# RF-CONNECTOR.net
KiCad netlist of a schematic drawn in Altium Designer
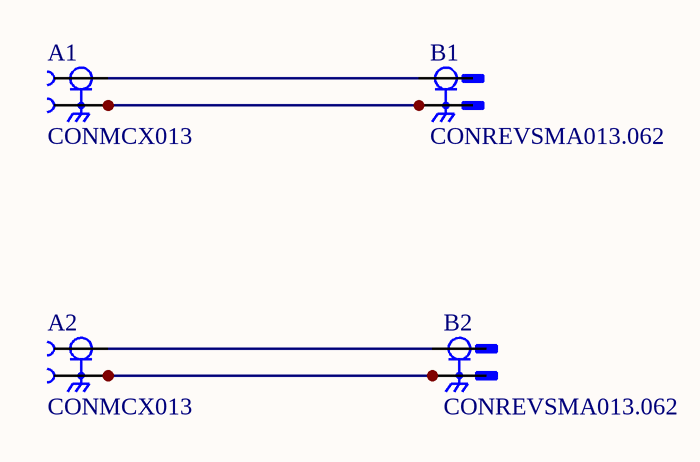
[diagram p0: RF-CONNECTOR.SchDoc]

(export (version "E")
  (design (tool "Eeschema 10.0.6"))
  (components
    (comp (ref "A1")
      (value "CONMCX013")
      (footprint "LINX_CONMCX013")
      (fields (field (name "MF") "Linx Technologies"))
      (libsource (lib "lib") (part "CONMCX013"))
    )
    (comp (ref "A2")
      (value "CONMCX013")
      (footprint "LINX_CONMCX013")
      (fields (field (name "MF") "Linx Technologies"))
      (libsource (lib "lib") (part "CONMCX013"))
    )
    (comp (ref "B1")
      (value "CONREVSMA013.062")
      (footprint "LINX_CONREVSMA013.031")
      (description "CONN RPSMA PLG STR 50OHM EDGEMNT")
      (fields (field (name "MF") "Linx"))
      (libsource (lib "lib") (part "CONREVSMA013.031"))
    )
    (comp (ref "B2")
      (value "CONREVSMA013.062")
      (footprint "LINX_CONREVSMA013.031")
      (description "CONN RPSMA PLG STR 50OHM EDGEMNT")
      (fields (field (name "MF") "Linx"))
      (libsource (lib "lib") (part "CONREVSMA013.031"))
    )
  )
  (nets
    (net (code "1") (name "Net-(A1-2-PadG1)") (class "Default")
      (node (ref "A1") (pin "G1") (pinfunction "2_G1") (pintype "passive"))
      (node (ref "A1") (pin "G2") (pinfunction "2_G2") (pintype "passive"))
      (node (ref "B1") (pin "S1") (pinfunction "2_S1") (pintype "passive"))
      (node (ref "B1") (pin "S2") (pinfunction "2_S2") (pintype "passive"))
      (node (ref "B1") (pin "S3") (pinfunction "2_S3") (pintype "passive"))
      (node (ref "B1") (pin "S4") (pinfunction "2_S4") (pintype "passive"))
    )
    (net (code "2") (name "Net-(A1-Pad1)") (class "Default")
      (node (ref "A1") (pin "1") (pinfunction "1_1") (pintype "passive"))
      (node (ref "B1") (pin "1") (pinfunction "1_1") (pintype "passive"))
    )
    (net (code "3") (name "Net-(A2-2-PadG1)") (class "Default")
      (node (ref "A2") (pin "G1") (pinfunction "2_G1") (pintype "passive"))
      (node (ref "A2") (pin "G2") (pinfunction "2_G2") (pintype "passive"))
      (node (ref "B2") (pin "S1") (pinfunction "2_S1") (pintype "passive"))
      (node (ref "B2") (pin "S2") (pinfunction "2_S2") (pintype "passive"))
      (node (ref "B2") (pin "S3") (pinfunction "2_S3") (pintype "passive"))
      (node (ref "B2") (pin "S4") (pinfunction "2_S4") (pintype "passive"))
    )
    (net (code "4") (name "Net-(A2-Pad1)") (class "Default")
      (node (ref "A2") (pin "1") (pinfunction "1_1") (pintype "passive"))
      (node (ref "B2") (pin "1") (pinfunction "1_1") (pintype "passive"))
    )
  )
)
